# connector.net
KiCad netlist of a schematic drawn in Altium Designer
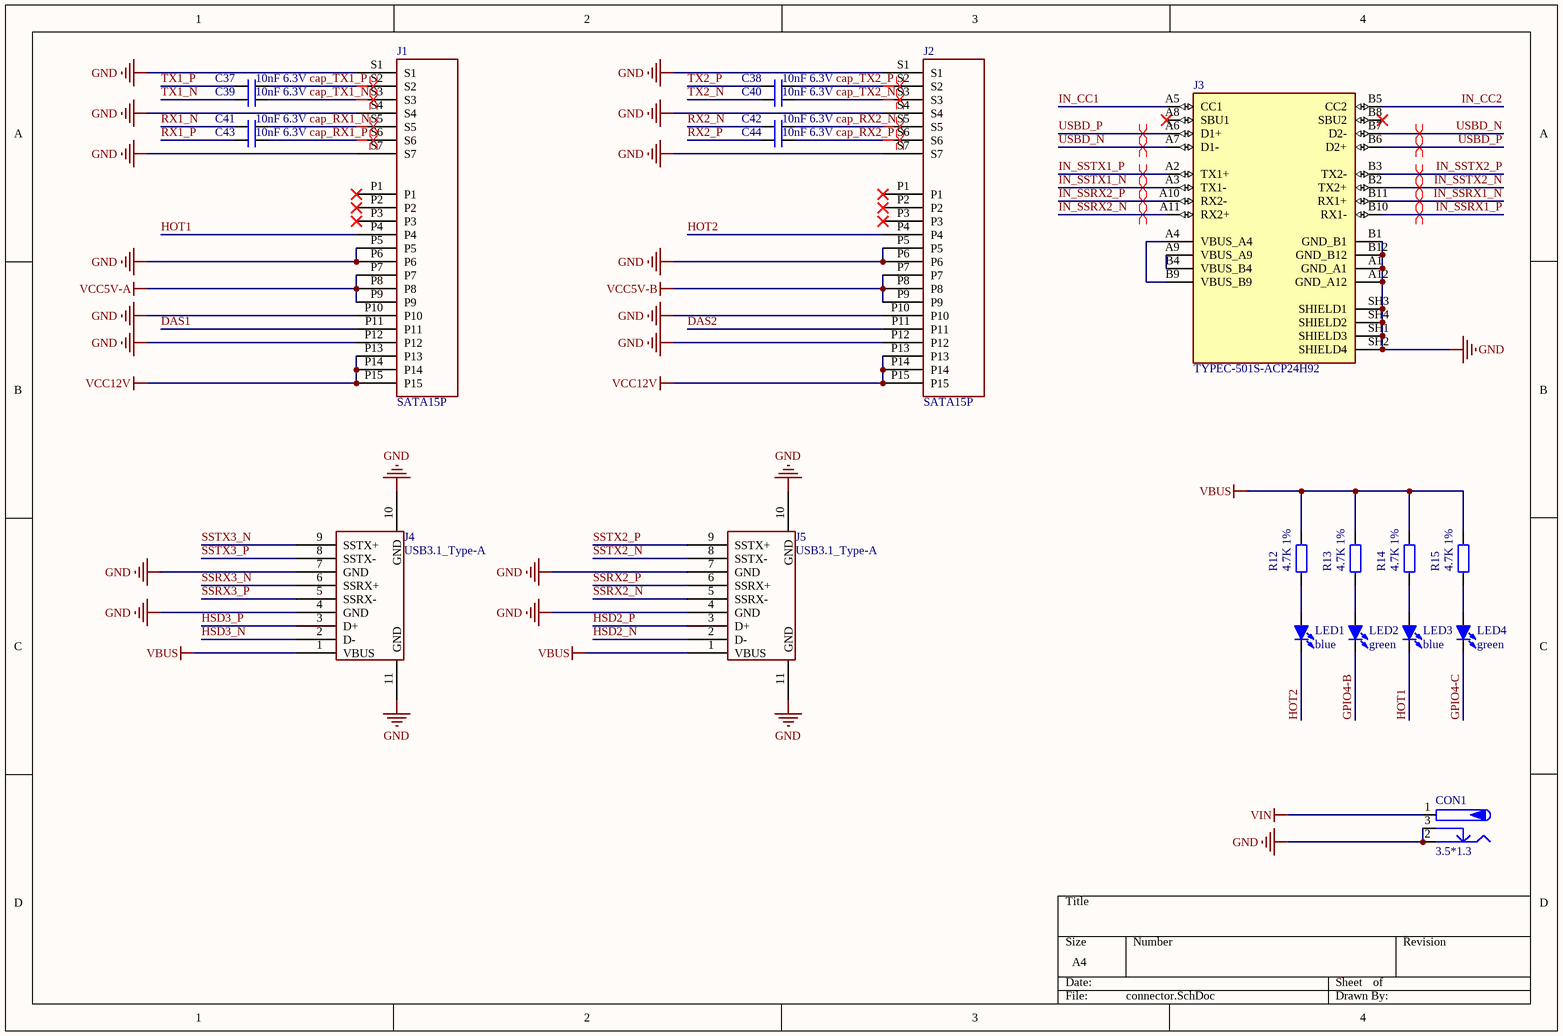
[diagram p0: connector.SchDoc]

(export (version "E")
  (design (tool "Eeschema 10.0.6"))
  (components
    (comp (ref "C37")
      (value "10nF 6.3V")
      (footprint "C0402_L")
      (description "无极性贴片电容")
      (fields (field (name "版权归属") "源创客"))
      (libsource (lib "Capacitor") (part "C"))
    )
    (comp (ref "C38")
      (value "10nF 6.3V")
      (footprint "C0402_L")
      (description "无极性贴片电容")
      (fields (field (name "版权归属") "源创客"))
      (libsource (lib "Capacitor") (part "C"))
    )
    (comp (ref "C39")
      (value "10nF 6.3V")
      (footprint "C0402_L")
      (description "无极性贴片电容")
      (fields (field (name "版权归属") "源创客"))
      (libsource (lib "Capacitor") (part "C"))
    )
    (comp (ref "C40")
      (value "10nF 6.3V")
      (footprint "C0402_L")
      (description "无极性贴片电容")
      (fields (field (name "版权归属") "源创客"))
      (libsource (lib "Capacitor") (part "C"))
    )
    (comp (ref "C41")
      (value "10nF 6.3V")
      (footprint "C0402_L")
      (description "无极性贴片电容")
      (fields (field (name "版权归属") "源创客"))
      (libsource (lib "Capacitor") (part "C"))
    )
    (comp (ref "C42")
      (value "10nF 6.3V")
      (footprint "C0402_L")
      (description "无极性贴片电容")
      (fields (field (name "版权归属") "源创客"))
      (libsource (lib "Capacitor") (part "C"))
    )
    (comp (ref "C43")
      (value "10nF 6.3V")
      (footprint "C0402_L")
      (description "无极性贴片电容")
      (fields (field (name "版权归属") "源创客"))
      (libsource (lib "Capacitor") (part "C"))
    )
    (comp (ref "C44")
      (value "10nF 6.3V")
      (footprint "C0402_L")
      (description "无极性贴片电容")
      (fields (field (name "版权归属") "源创客"))
      (libsource (lib "Capacitor") (part "C"))
    )
    (comp (ref "CON1")
      (value "3.5*1.3")
      (footprint "DC-IN-SMD_DC-182-25A")
      (description "低压电源接口")
      (fields (field (name "版权归属") "源创客"))
      (libsource (lib "Connector-PWR") (part "P-DC"))
    )
    (comp (ref "J1")
      (value "SATA15P")
      (footprint "SATA 15P 贴片")
      (libsource (lib "Connector-SATA&SAS") (part "SATA15P"))
    )
    (comp (ref "J2")
      (value "SATA15P")
      (footprint "SATA 15P 贴片")
      (libsource (lib "Connector-SATA&SAS") (part "SATA15P"))
    )
    (comp (ref "J3")
      (value "TYPEC-501S-ACP24H92")
      (footprint "TypeC 24p 直立")
      (fields (field (name "MF") "Molex") (field (name "MP") "1054500101"))
      (libsource (lib "Connector-USB") (part "Typec 24p"))
    )
    (comp (ref "J4")
      (value "USB3.1_Type-A")
      (footprint "USB3.1_Type-A 立式直插")
      (description "USB接口")
      (libsource (lib "Connector-USB") (part "USB3.1_Type-A"))
    )
    (comp (ref "J5")
      (value "USB3.1_Type-A")
      (footprint "USB3.1_Type-A 立式直插")
      (description "USB接口")
      (libsource (lib "Connector-USB") (part "USB3.1_Type-A"))
    )
    (comp (ref "LED1")
      (value "blue")
      (footprint "LED 0805B")
      (description "插件LED")
      (fields (field (name "版权归属") "源创客"))
      (libsource (lib "LED") (part "LED-3MM"))
    )
    (comp (ref "LED2")
      (value "green")
      (footprint "LED 0805G")
      (description "插件LED")
      (fields (field (name "版权归属") "源创客"))
      (libsource (lib "LED") (part "LED-3MM"))
    )
    (comp (ref "LED3")
      (value "blue")
      (footprint "LED 0805B")
      (description "插件LED")
      (fields (field (name "版权归属") "源创客"))
      (libsource (lib "LED") (part "LED-3MM"))
    )
    (comp (ref "LED4")
      (value "green")
      (footprint "LED 0805G")
      (description "插件LED")
      (fields (field (name "版权归属") "源创客"))
      (libsource (lib "LED") (part "LED-3MM"))
    )
    (comp (ref "R12")
      (value "4.7K 1%")
      (footprint "R0402_L")
      (description "贴片电阻")
      (fields (field (name "版权归属") "源创客"))
      (libsource (lib "Resistor") (part "R"))
    )
    (comp (ref "R13")
      (value "4.7K 1%")
      (footprint "R0402_L")
      (description "贴片电阻")
      (fields (field (name "版权归属") "源创客"))
      (libsource (lib "Resistor") (part "R"))
    )
    (comp (ref "R14")
      (value "4.7K 1%")
      (footprint "R0402_L")
      (description "贴片电阻")
      (fields (field (name "版权归属") "源创客"))
      (libsource (lib "Resistor") (part "R"))
    )
    (comp (ref "R15")
      (value "4.7K 1%")
      (footprint "R0402_L")
      (description "贴片电阻")
      (fields (field (name "版权归属") "源创客"))
      (libsource (lib "Resistor") (part "R"))
    )
  )
  (nets
    (net (code "1") (name "/DAS1") (class "Default")
      (node (ref "J1") (pin "P11") (pinfunction "P11_P11") (pintype "passive"))
    )
    (net (code "2") (name "/DAS2") (class "Default")
      (node (ref "J2") (pin "P11") (pinfunction "P11_P11") (pintype "passive"))
    )
    (net (code "3") (name "/GPIO4-B") (class "Default")
      (node (ref "LED2") (pin "2") (pinfunction "K_2") (pintype "passive"))
    )
    (net (code "4") (name "/GPIO4-C") (class "Default")
      (node (ref "LED4") (pin "2") (pinfunction "K_2") (pintype "passive"))
    )
    (net (code "5") (name "/HOT1") (class "Default")
      (node (ref "J1") (pin "P4") (pinfunction "P4_P4") (pintype "passive"))
      (node (ref "LED3") (pin "2") (pinfunction "K_2") (pintype "passive"))
    )
    (net (code "6") (name "/HOT2") (class "Default")
      (node (ref "J2") (pin "P4") (pinfunction "P4_P4") (pintype "passive"))
      (node (ref "LED1") (pin "2") (pinfunction "K_2") (pintype "passive"))
    )
    (net (code "7") (name "/HSD2_N") (class "Default")
      (node (ref "J5") (pin "2") (pinfunction "D-_2") (pintype "passive"))
    )
    (net (code "8") (name "/HSD2_P") (class "Default")
      (node (ref "J5") (pin "3") (pinfunction "D+_3") (pintype "passive"))
    )
    (net (code "9") (name "/HSD3_N") (class "Default")
      (node (ref "J4") (pin "2") (pinfunction "D-_2") (pintype "passive"))
    )
    (net (code "10") (name "/HSD3_P") (class "Default")
      (node (ref "J4") (pin "3") (pinfunction "D+_3") (pintype "passive"))
    )
    (net (code "11") (name "/IN_CC1") (class "Default")
      (node (ref "J3") (pin "A5") (pinfunction "CC1_A5") (pintype "bidirectional"))
    )
    (net (code "12") (name "/IN_CC2") (class "Default")
      (node (ref "J3") (pin "B5") (pinfunction "CC2_B5") (pintype "bidirectional"))
    )
    (net (code "13") (name "/IN_SSRX1_N") (class "Default")
      (node (ref "J3") (pin "B11") (pinfunction "RX1+_B11") (pintype "bidirectional"))
    )
    (net (code "14") (name "/IN_SSRX1_P") (class "Default")
      (node (ref "J3") (pin "B10") (pinfunction "RX1-_B10") (pintype "bidirectional"))
    )
    (net (code "15") (name "/IN_SSRX2_N") (class "Default")
      (node (ref "J3") (pin "A11") (pinfunction "RX2+_A11") (pintype "bidirectional"))
    )
    (net (code "16") (name "/IN_SSRX2_P") (class "Default")
      (node (ref "J3") (pin "A10") (pinfunction "RX2-_A10") (pintype "bidirectional"))
    )
    (net (code "17") (name "/IN_SSTX1_N") (class "Default")
      (node (ref "J3") (pin "A3") (pinfunction "TX1-_A3") (pintype "bidirectional"))
    )
    (net (code "18") (name "/IN_SSTX1_P") (class "Default")
      (node (ref "J3") (pin "A2") (pinfunction "TX1+_A2") (pintype "bidirectional"))
    )
    (net (code "19") (name "/IN_SSTX2_N") (class "Default")
      (node (ref "J3") (pin "B2") (pinfunction "TX2+_B2") (pintype "bidirectional"))
    )
    (net (code "20") (name "/IN_SSTX2_P") (class "Default")
      (node (ref "J3") (pin "B3") (pinfunction "TX2-_B3") (pintype "bidirectional"))
    )
    (net (code "21") (name "/RX1_N") (class "Default")
      (node (ref "C41") (pin "2") (pinfunction "2_2") (pintype "passive"))
    )
    (net (code "22") (name "/RX1_P") (class "Default")
      (node (ref "C43") (pin "2") (pinfunction "2_2") (pintype "passive"))
    )
    (net (code "23") (name "/RX2_N") (class "Default")
      (node (ref "C42") (pin "2") (pinfunction "2_2") (pintype "passive"))
    )
    (net (code "24") (name "/RX2_P") (class "Default")
      (node (ref "C44") (pin "2") (pinfunction "2_2") (pintype "passive"))
    )
    (net (code "25") (name "/SSRX2_N") (class "Default")
      (node (ref "J5") (pin "5") (pinfunction "SSRX-_5") (pintype "passive"))
    )
    (net (code "26") (name "/SSRX2_P") (class "Default")
      (node (ref "J5") (pin "6") (pinfunction "SSRX+_6") (pintype "passive"))
    )
    (net (code "27") (name "/SSRX3_N") (class "Default")
      (node (ref "J4") (pin "6") (pinfunction "SSRX+_6") (pintype "passive"))
    )
    (net (code "28") (name "/SSRX3_P") (class "Default")
      (node (ref "J4") (pin "5") (pinfunction "SSRX-_5") (pintype "passive"))
    )
    (net (code "29") (name "/SSTX2_N") (class "Default")
      (node (ref "J5") (pin "8") (pinfunction "SSTX-_8") (pintype "passive"))
    )
    (net (code "30") (name "/SSTX2_P") (class "Default")
      (node (ref "J5") (pin "9") (pinfunction "SSTX+_9") (pintype "passive"))
    )
    (net (code "31") (name "/SSTX3_N") (class "Default")
      (node (ref "J4") (pin "9") (pinfunction "SSTX+_9") (pintype "passive"))
    )
    (net (code "32") (name "/SSTX3_P") (class "Default")
      (node (ref "J4") (pin "8") (pinfunction "SSTX-_8") (pintype "passive"))
    )
    (net (code "33") (name "/TX1_N") (class "Default")
      (node (ref "C39") (pin "2") (pinfunction "2_2") (pintype "passive"))
    )
    (net (code "34") (name "/TX1_P") (class "Default")
      (node (ref "C37") (pin "2") (pinfunction "2_2") (pintype "passive"))
    )
    (net (code "35") (name "/TX2_N") (class "Default")
      (node (ref "C40") (pin "2") (pinfunction "2_2") (pintype "passive"))
    )
    (net (code "36") (name "/TX2_P") (class "Default")
      (node (ref "C38") (pin "2") (pinfunction "2_2") (pintype "passive"))
    )
    (net (code "37") (name "/USBD_N") (class "Default")
      (node (ref "J3") (pin "A7") (pinfunction "D1-_A7") (pintype "bidirectional"))
      (node (ref "J3") (pin "B7") (pinfunction "D2-_B7") (pintype "bidirectional"))
    )
    (net (code "38") (name "/USBD_P") (class "Default")
      (node (ref "J3") (pin "A6") (pinfunction "D1+_A6") (pintype "bidirectional"))
      (node (ref "J3") (pin "B6") (pinfunction "D2+_B6") (pintype "bidirectional"))
    )
    (net (code "39") (name "/cap_RX1_N") (class "Default")
      (node (ref "C41") (pin "1") (pinfunction "1_1") (pintype "passive"))
      (node (ref "J1") (pin "S5") (pinfunction "S5_S5") (pintype "passive"))
    )
    (net (code "40") (name "/cap_RX1_P") (class "Default")
      (node (ref "C43") (pin "1") (pinfunction "1_1") (pintype "passive"))
      (node (ref "J1") (pin "S6") (pinfunction "S6_S6") (pintype "passive"))
    )
    (net (code "41") (name "/cap_RX2_N") (class "Default")
      (node (ref "C42") (pin "1") (pinfunction "1_1") (pintype "passive"))
      (node (ref "J2") (pin "S5") (pinfunction "S5_S5") (pintype "passive"))
    )
    (net (code "42") (name "/cap_RX2_P") (class "Default")
      (node (ref "C44") (pin "1") (pinfunction "1_1") (pintype "passive"))
      (node (ref "J2") (pin "S6") (pinfunction "S6_S6") (pintype "passive"))
    )
    (net (code "43") (name "/cap_TX1_N") (class "Default")
      (node (ref "C39") (pin "1") (pinfunction "1_1") (pintype "passive"))
      (node (ref "J1") (pin "S3") (pinfunction "S3_S3") (pintype "passive"))
    )
    (net (code "44") (name "/cap_TX1_P") (class "Default")
      (node (ref "C37") (pin "1") (pinfunction "1_1") (pintype "passive"))
      (node (ref "J1") (pin "S2") (pinfunction "S2_S2") (pintype "passive"))
    )
    (net (code "45") (name "/cap_TX2_N") (class "Default")
      (node (ref "C40") (pin "1") (pinfunction "1_1") (pintype "passive"))
      (node (ref "J2") (pin "S3") (pinfunction "S3_S3") (pintype "passive"))
    )
    (net (code "46") (name "/cap_TX2_P") (class "Default")
      (node (ref "C38") (pin "1") (pinfunction "1_1") (pintype "passive"))
      (node (ref "J2") (pin "S2") (pinfunction "S2_S2") (pintype "passive"))
    )
    (net (code "47") (name "GND") (class "Default")
      (node (ref "CON1") (pin "2") (pintype "power_in"))
      (node (ref "CON1") (pin "3") (pintype "power_in"))
      (node (ref "J1") (pin "P10") (pinfunction "P10_P10") (pintype "passive"))
      (node (ref "J1") (pin "P12") (pinfunction "P12_P12") (pintype "passive"))
      (node (ref "J1") (pin "P5") (pinfunction "P5_P5") (pintype "passive"))
      (node (ref "J1") (pin "P6") (pinfunction "P6_P6") (pintype "passive"))
      (node (ref "J1") (pin "S1") (pinfunction "S1_S1") (pintype "passive"))
      (node (ref "J1") (pin "S4") (pinfunction "S4_S4") (pintype "passive"))
      (node (ref "J1") (pin "S7") (pinfunction "S7_S7") (pintype "passive"))
      (node (ref "J2") (pin "P10") (pinfunction "P10_P10") (pintype "passive"))
      (node (ref "J2") (pin "P12") (pinfunction "P12_P12") (pintype "passive"))
      (node (ref "J2") (pin "P5") (pinfunction "P5_P5") (pintype "passive"))
      (node (ref "J2") (pin "P6") (pinfunction "P6_P6") (pintype "passive"))
      (node (ref "J2") (pin "S1") (pinfunction "S1_S1") (pintype "passive"))
      (node (ref "J2") (pin "S4") (pinfunction "S4_S4") (pintype "passive"))
      (node (ref "J2") (pin "S7") (pinfunction "S7_S7") (pintype "passive"))
      (node (ref "J3") (pin "A1") (pinfunction "GND_A1_A1") (pintype "power_in"))
      (node (ref "J3") (pin "A12") (pinfunction "GND_A12_A12") (pintype "power_in"))
      (node (ref "J3") (pin "B1") (pinfunction "GND_B1_B1") (pintype "power_in"))
      (node (ref "J3") (pin "B12") (pinfunction "GND_B12_B12") (pintype "power_in"))
      (node (ref "J3") (pin "SH1") (pinfunction "SHIELD3_SH1") (pintype "passive"))
      (node (ref "J3") (pin "SH2") (pinfunction "SHIELD4_SH2") (pintype "passive"))
      (node (ref "J3") (pin "SH3") (pinfunction "SHIELD1_SH3") (pintype "passive"))
      (node (ref "J3") (pin "SH4") (pinfunction "SHIELD2_SH4") (pintype "passive"))
      (node (ref "J4") (pin "10") (pinfunction "GND_10") (pintype "passive"))
      (node (ref "J4") (pin "11") (pinfunction "GND_11") (pintype "passive"))
      (node (ref "J4") (pin "4") (pinfunction "GND_4") (pintype "passive"))
      (node (ref "J4") (pin "7") (pinfunction "GND_7") (pintype "passive"))
      (node (ref "J5") (pin "10") (pinfunction "GND_10") (pintype "passive"))
      (node (ref "J5") (pin "11") (pinfunction "GND_11") (pintype "passive"))
      (node (ref "J5") (pin "4") (pinfunction "GND_4") (pintype "passive"))
      (node (ref "J5") (pin "7") (pinfunction "GND_7") (pintype "passive"))
    )
    (net (code "48") (name "Net-(J3-VBUS_A4)") (class "Default")
      (node (ref "J3") (pin "A4") (pinfunction "VBUS_A4_A4") (pintype "power_in"))
      (node (ref "J3") (pin "B9") (pinfunction "VBUS_B9_B9") (pintype "power_in"))
    )
    (net (code "49") (name "Net-(J3-VBUS_A9)") (class "Default")
      (node (ref "J3") (pin "A9") (pinfunction "VBUS_A9_A9") (pintype "power_in"))
      (node (ref "J3") (pin "B4") (pinfunction "VBUS_B4_B4") (pintype "power_in"))
    )
    (net (code "50") (name "Net-(LED1-A)") (class "Default")
      (node (ref "LED1") (pin "1") (pinfunction "A_1") (pintype "passive"))
      (node (ref "R12") (pin "2") (pinfunction "2_2") (pintype "passive"))
    )
    (net (code "51") (name "Net-(LED2-A)") (class "Default")
      (node (ref "LED2") (pin "1") (pinfunction "A_1") (pintype "passive"))
      (node (ref "R13") (pin "2") (pinfunction "2_2") (pintype "passive"))
    )
    (net (code "52") (name "Net-(LED3-A)") (class "Default")
      (node (ref "LED3") (pin "1") (pinfunction "A_1") (pintype "passive"))
      (node (ref "R14") (pin "2") (pinfunction "2_2") (pintype "passive"))
    )
    (net (code "53") (name "Net-(LED4-A)") (class "Default")
      (node (ref "LED4") (pin "1") (pinfunction "A_1") (pintype "passive"))
      (node (ref "R15") (pin "2") (pinfunction "2_2") (pintype "passive"))
    )
    (net (code "54") (name "VBUS") (class "Default")
      (node (ref "J4") (pin "1") (pinfunction "VBUS_1") (pintype "passive"))
      (node (ref "J5") (pin "1") (pinfunction "VBUS_1") (pintype "passive"))
      (node (ref "R12") (pin "1") (pinfunction "1_1") (pintype "passive"))
      (node (ref "R13") (pin "1") (pinfunction "1_1") (pintype "passive"))
      (node (ref "R14") (pin "1") (pinfunction "1_1") (pintype "passive"))
      (node (ref "R15") (pin "1") (pinfunction "1_1") (pintype "passive"))
    )
    (net (code "55") (name "VCC5V-A") (class "Default")
      (node (ref "J1") (pin "P7") (pinfunction "P7_P7") (pintype "passive"))
      (node (ref "J1") (pin "P8") (pinfunction "P8_P8") (pintype "passive"))
      (node (ref "J1") (pin "P9") (pinfunction "P9_P9") (pintype "passive"))
    )
    (net (code "56") (name "VCC5V-B") (class "Default")
      (node (ref "J2") (pin "P7") (pinfunction "P7_P7") (pintype "passive"))
      (node (ref "J2") (pin "P8") (pinfunction "P8_P8") (pintype "passive"))
      (node (ref "J2") (pin "P9") (pinfunction "P9_P9") (pintype "passive"))
    )
    (net (code "57") (name "VCC12V") (class "Default")
      (node (ref "J1") (pin "P13") (pinfunction "P13_P13") (pintype "passive"))
      (node (ref "J1") (pin "P14") (pinfunction "P14_P14") (pintype "passive"))
      (node (ref "J1") (pin "P15") (pinfunction "P15_P15") (pintype "passive"))
      (node (ref "J2") (pin "P13") (pinfunction "P13_P13") (pintype "passive"))
      (node (ref "J2") (pin "P14") (pinfunction "P14_P14") (pintype "passive"))
      (node (ref "J2") (pin "P15") (pinfunction "P15_P15") (pintype "passive"))
    )
    (net (code "58") (name "VIN") (class "Default") (node (ref "CON1") (pin "1") (pintype "power_in")))
    (net (code "59") (name "unconnected-(J1-PadP1)") (class "Default")
      (node (ref "J1") (pin "P1") (pinfunction "P1_P1") (pintype "passive+no_connect"))
    )
    (net (code "60") (name "unconnected-(J1-PadP2)") (class "Default")
      (node (ref "J1") (pin "P2") (pinfunction "P2_P2") (pintype "passive+no_connect"))
    )
    (net (code "61") (name "unconnected-(J1-PadP3)") (class "Default")
      (node (ref "J1") (pin "P3") (pinfunction "P3_P3") (pintype "passive+no_connect"))
    )
    (net (code "62") (name "unconnected-(J2-PadP1)") (class "Default")
      (node (ref "J2") (pin "P1") (pinfunction "P1_P1") (pintype "passive+no_connect"))
    )
    (net (code "63") (name "unconnected-(J2-PadP2)") (class "Default")
      (node (ref "J2") (pin "P2") (pinfunction "P2_P2") (pintype "passive+no_connect"))
    )
    (net (code "64") (name "unconnected-(J2-PadP3)") (class "Default")
      (node (ref "J2") (pin "P3") (pinfunction "P3_P3") (pintype "passive+no_connect"))
    )
    (net (code "65") (name "unconnected-(J3-SBU1-PadA8)") (class "Default")
      (node (ref "J3") (pin "A8") (pinfunction "SBU1_A8") (pintype "bidirectional+no_connect"))
    )
    (net (code "66") (name "unconnected-(J3-SBU2-PadB8)") (class "Default")
      (node (ref "J3") (pin "B8") (pinfunction "SBU2_B8") (pintype "bidirectional+no_connect"))
    )
  )
)
